# MOSFET_Driver.net
KiCad netlist of a schematic drawn in Altium Designer
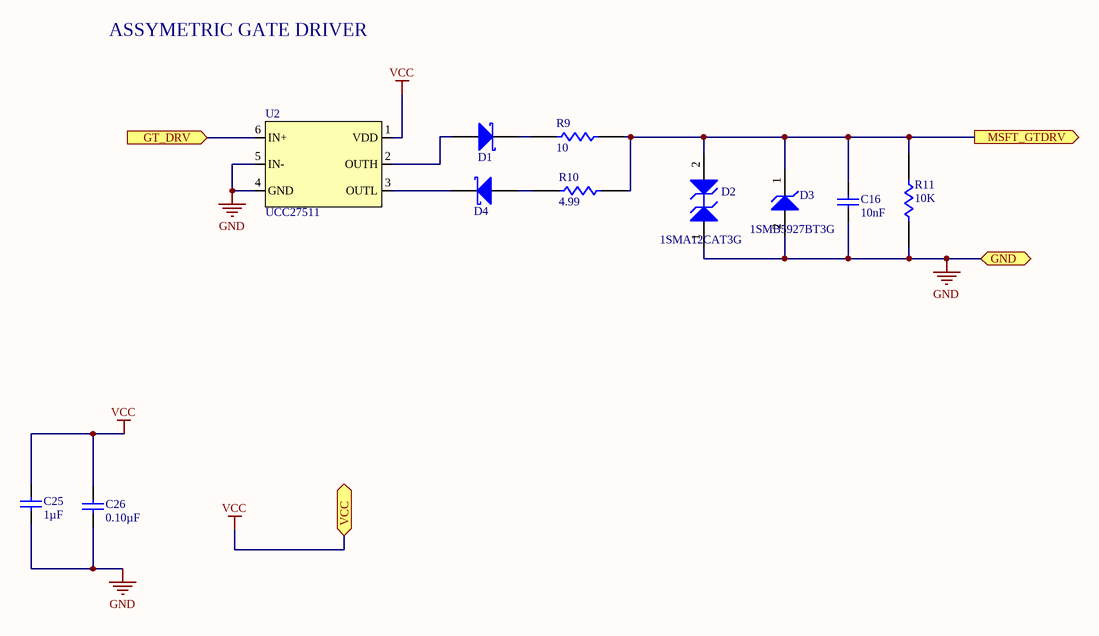
[diagram p0: MOSFET Driver.SchDoc]

(export (version "E")
  (design (tool "Eeschema 10.0.6"))
  (components
    (comp (ref "C16")
      (value "10nF")
      (footprint "CAP0603")
      (description "CAP CER 10000PF 25V C0G/NP0 0603")
      (fields
        (field (name "MANUFACTURER") "KEMET")
        (field (name "MANUFACTURER PART NUMBER") "C0603C103F3GACTU")
      )
      (libsource (lib "ucc28180-V03") (part "C0603C103F3GACTU"))
    )
    (comp (ref "C25")
      (value "GRM32RR71H105KA01K")
      (footprint "CAP1210")
      (description "CAP CER 1UF 50V X7R 1210")
      (fields (field (name "TOLERANCE") "±10%") (field (name "CAPACITANCE") "1µF"))
      (libsource (lib "ucc28180-V03") (part "GRM32RR71H105KA01K"))
    )
    (comp (ref "C26")
      (value "06035C104KAT2A")
      (footprint "CAP0603")
      (description "CAP CER 0.1UF 50V X7R 0603")
      (fields (field (name "TOLERANCE") "±10%") (field (name "CAPACITANCE") "0.10µF"))
      (libsource (lib "ucc28180-V03") (part "06035C104KAT2A"))
    )
    (comp (ref "D1")
      (value "DB2W40300L")
      (footprint "Mini2-F3-B")
      (fields (field (name "MANUFACTURER") "Panasonic"))
      (libsource (lib "ucc28180") (part "DB2W40300L"))
    )
    (comp (ref "D2")
      (value "1SMA12CAT3G")
      (footprint "ONSC-SMA-2-403D-02_F_V")
      (description "400 W Peak Power Zener Transient Voltage Suppressor, 2-Pin SMA, Pb-Free, Tape and Reel")
      (fields (field (name "MANUFACTURER") "On Semiconductor"))
      (libsource (lib "ON Semi Transient Voltage Suppressors (TVS)") (part "1SMA12CAT3G"))
    )
    (comp (ref "D3")
      (value "1SMB5927BT3G")
      (footprint "ONSC-SMB-2-403A-03_H_V")
      (description "3 W Zener Voltage Regulator, 2-Pin SMB, Pb-Free, Tape and Reel")
      (fields (field (name "MANUFACTURER") "On Semiconductor"))
      (libsource (lib "ON Semi Zener Diodes") (part "1SMB5927BT3G"))
    )
    (comp (ref "D4")
      (value "DB2W40300L")
      (footprint "Mini2-F3-B")
      (fields (field (name "MANUFACTURER") "Panasonic"))
      (libsource (lib "ucc28180") (part "DB2W40300L"))
    )
    (comp (ref "R9")
      (value "CRCW0805R10")
      (footprint "RES0805")
      (fields (field (name "RESISTANCE") "10"))
      (libsource (lib "ucc28180") (part "CRCW0805R10"))
    )
    (comp (ref "R10")
      (value "CRCW0805R4.99")
      (footprint "RES0805")
      (fields (field (name "RESISTANCE") "4.99"))
      (libsource (lib "ucc28180") (part "CRCW0805R4.99"))
    )
    (comp (ref "R11")
      (value "CRCW0603RES10K")
      (footprint "RES0603")
      (fields (field (name "RESISTANCE") "10K"))
      (libsource (lib "ucc28180") (part "CRCW0603RES10K"))
    )
    (comp (ref "U2")
      (value "UCC27511DBV")
      (footprint "SOP6")
      (fields (field (name "IC NAME") "UCC27511"))
      (libsource (lib "ucc28180") (part "UCC27511DBV"))
    )
  )
  (nets
    (net (code "1") (name "/GT_DRV") (class "Default")
      (node (ref "U2") (pin "6") (pinfunction "IN+_6") (pintype "input"))
    )
    (net (code "2") (name "/MSFT_GTDRV") (class "Default")
      (node (ref "C16") (pin "2") (pinfunction "2_2") (pintype "passive"))
      (node (ref "D2") (pin "2") (pinfunction "A2_2") (pintype "passive"))
      (node (ref "D3") (pin "1") (pinfunction "K_1") (pintype "passive"))
      (node (ref "R10") (pin "1") (pinfunction "1_1") (pintype "passive"))
      (node (ref "R11") (pin "1") (pinfunction "1_1") (pintype "passive"))
      (node (ref "R9") (pin "1") (pinfunction "1_1") (pintype "passive"))
    )
    (net (code "3") (name "GND") (class "Default")
      (node (ref "C16") (pin "1") (pinfunction "1_1") (pintype "passive"))
      (node (ref "C25") (pin "1") (pinfunction "1_1") (pintype "passive"))
      (node (ref "C26") (pin "1") (pinfunction "1_1") (pintype "passive"))
      (node (ref "D2") (pin "1") (pinfunction "A1_1") (pintype "passive"))
      (node (ref "D3") (pin "2") (pinfunction "A_2") (pintype "passive"))
      (node (ref "R11") (pin "2") (pinfunction "2_2") (pintype "passive"))
      (node (ref "U2") (pin "4") (pinfunction "GND_4") (pintype "passive"))
      (node (ref "U2") (pin "5") (pinfunction "IN-_5") (pintype "input"))
    )
    (net (code "4") (name "Net-(D1-A)") (class "Default")
      (node (ref "D1") (pin "3") (pinfunction "A_3") (pintype "passive"))
      (node (ref "U2") (pin "2") (pinfunction "OUTH_2") (pintype "output"))
    )
    (net (code "5") (name "Net-(D1-K)") (class "Default")
      (node (ref "D1") (pin "1") (pinfunction "K_1") (pintype "passive"))
      (node (ref "R9") (pin "2") (pinfunction "2_2") (pintype "passive"))
    )
    (net (code "6") (name "Net-(D4-A)") (class "Default")
      (node (ref "D4") (pin "3") (pinfunction "A_3") (pintype "passive"))
      (node (ref "R10") (pin "2") (pinfunction "2_2") (pintype "passive"))
    )
    (net (code "7") (name "Net-(D4-K)") (class "Default")
      (node (ref "D4") (pin "1") (pinfunction "K_1") (pintype "passive"))
      (node (ref "U2") (pin "3") (pinfunction "OUTL_3") (pintype "output"))
    )
    (net (code "8") (name "VCC") (class "Default")
      (node (ref "C25") (pin "2") (pinfunction "2_2") (pintype "passive"))
      (node (ref "C26") (pin "2") (pinfunction "2_2") (pintype "passive"))
      (node (ref "U2") (pin "1") (pinfunction "VDD_1") (pintype "passive"))
    )
  )
)
